# new-mainboard.net
KiCad netlist of a schematic drawn in EAGLE
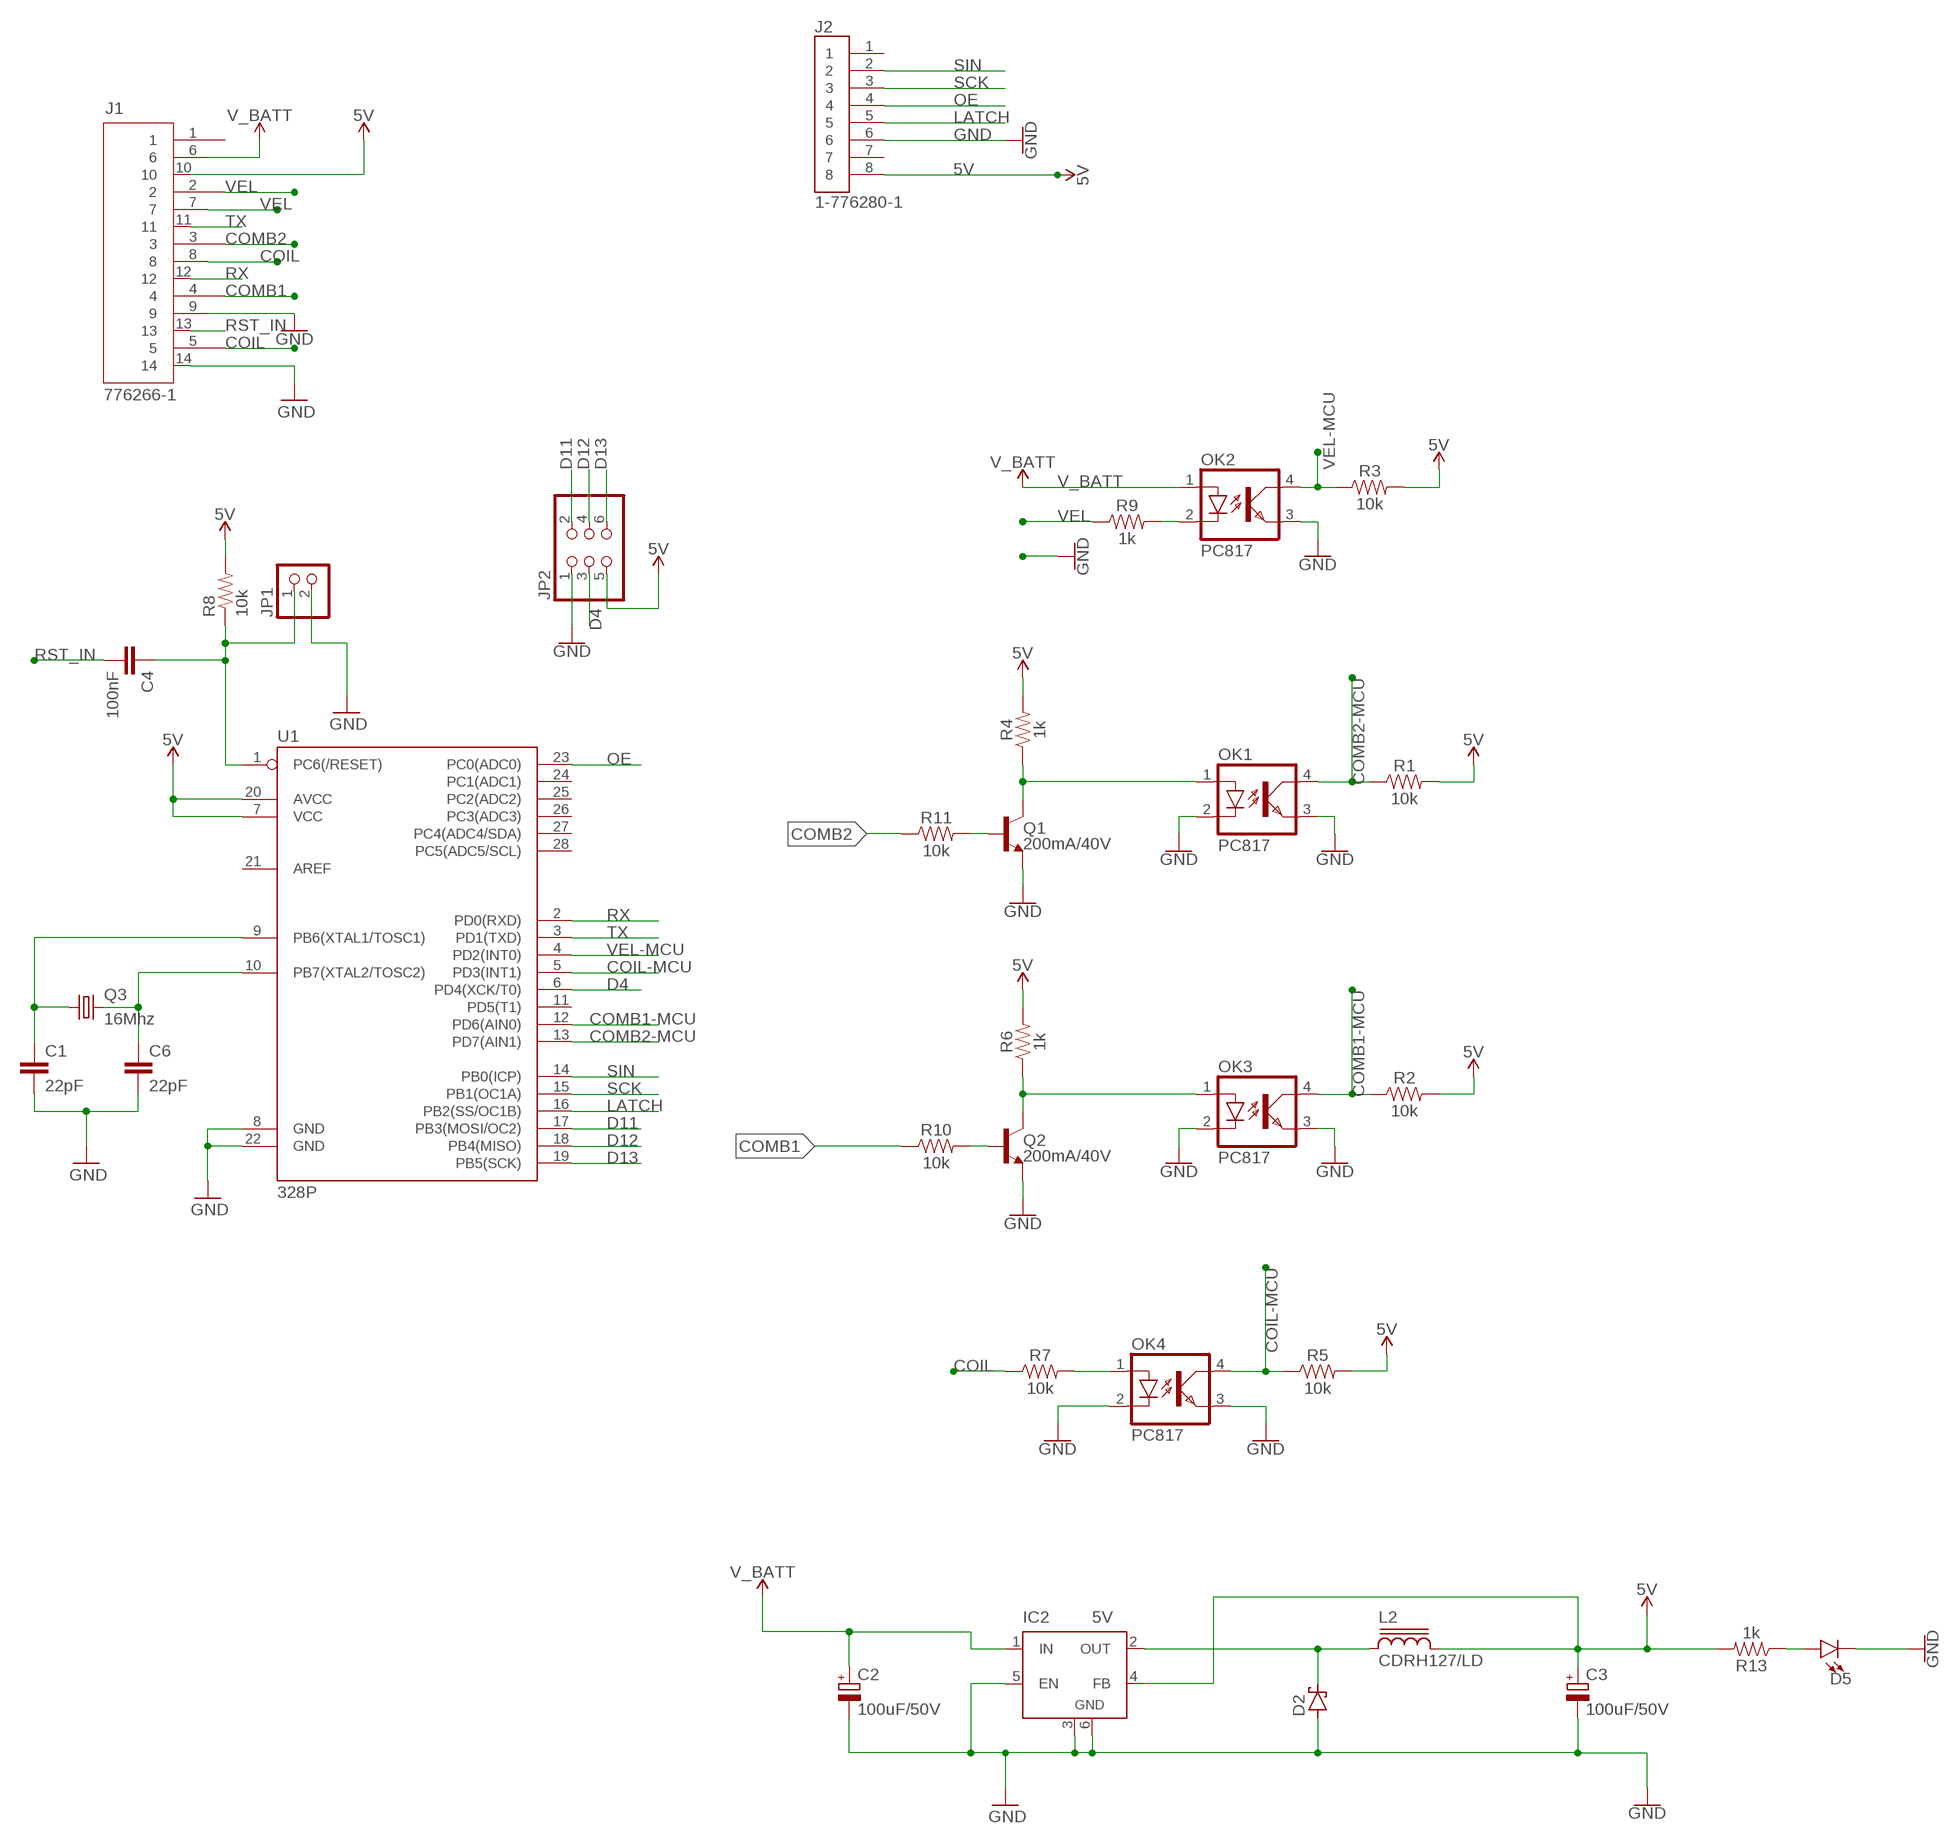
[diagram p0: schematic, sheet 1]

(export (version "E")
  (design (tool "Eeschema 10.0.6"))
  (components
    (comp (ref "C1")
      (value "22pF")
      (footprint "eagle-import:CAP-PTH-2.54")
      (libsource (lib "eagle-import") (part "22PF-PTH-2.54MM-200V-5%"))
    )
    (comp (ref "C2")
      (value "100uF/50V")
      (footprint "eagle-import:E3,5-8")
      (libsource (lib "eagle-import") (part "CPOL-EUE3.5-8"))
    )
    (comp (ref "C3")
      (value "100uF/50V")
      (footprint "eagle-import:E3,5-8")
      (libsource (lib "eagle-import") (part "CPOL-EUE3.5-8"))
    )
    (comp (ref "C4")
      (value "100nF")
      (footprint "eagle-import:CAP-PTH-2.54")
      (libsource (lib "eagle-import") (part "22PF-PTH-2.54MM-200V-5%"))
    )
    (comp (ref "C6")
      (value "22pF")
      (footprint "eagle-import:CAP-PTH-2.54")
      (libsource (lib "eagle-import") (part "22PF-PTH-2.54MM-200V-5%"))
    )
    (comp (ref "D2")
      (value "SCHOTTKY-DIODESMD")
      (footprint "eagle-import:SMB")
      (libsource (lib "eagle-import") (part "SCHOTTKY-DIODESMD"))
    )
    (comp (ref "D5")
      (value "LED3MM")
      (footprint "eagle-import:LED_3MM")
      (libsource (lib "eagle-import") (part "LED3MM"))
    )
    (comp (ref "IC2")
      (value "5V")
      (footprint "eagle-import:TO263-5")
      (libsource (lib "eagle-import") (part "LM2596S"))
    )
    (comp (ref "J1")
      (value "776266-1")
      (footprint "eagle-import:TE_776266-1")
      (fields (field (name "MANUFACTURER") "TE CONNECTIVITY"))
      (libsource (lib "eagle-import") (part "776266-1"))
    )
    (comp (ref "J2")
      (value "1-776280-1")
      (footprint "eagle-import:TE_1-776280-1")
      (fields (field (name "MANUFACTURER") "TE Connectivity"))
      (libsource (lib "eagle-import") (part "1-776280-1"))
    )
    (comp (ref "JP1")
      (value "PINHD-1X2")
      (footprint "eagle-import:1X02")
      (libsource (lib "eagle-import") (part "PINHD-1X2"))
    )
    (comp (ref "JP2")
      (value "PINHD-2X3")
      (footprint "eagle-import:2X03")
      (libsource (lib "eagle-import") (part "PINHD-2X3"))
    )
    (comp (ref "L2")
      (value "CDRH127/LD")
      (footprint "eagle-import:CDRH127_LD")
      (libsource (lib "eagle-import") (part "CDRH127/LD"))
    )
    (comp (ref "OK1")
      (value "PC817")
      (footprint "eagle-import:DIL04")
      (fields (field (name "MPN") "PC817X4J000F"))
      (libsource (lib "eagle-import") (part "PC817"))
    )
    (comp (ref "OK2")
      (value "PC817")
      (footprint "eagle-import:DIL04")
      (fields (field (name "MPN") "PC817X4J000F"))
      (libsource (lib "eagle-import") (part "PC817"))
    )
    (comp (ref "OK3")
      (value "PC817")
      (footprint "eagle-import:DIL04")
      (fields (field (name "MPN") "PC817X4J000F"))
      (libsource (lib "eagle-import") (part "PC817"))
    )
    (comp (ref "OK4")
      (value "PC817")
      (footprint "eagle-import:DIL04")
      (fields (field (name "MPN") "PC817X4J000F"))
      (libsource (lib "eagle-import") (part "PC817"))
    )
    (comp (ref "Q1")
      (value "200mA/40V")
      (footprint "eagle-import:TO-92")
      (libsource (lib "eagle-import") (part "TRANS_NPN-2N3904"))
    )
    (comp (ref "Q2")
      (value "200mA/40V")
      (footprint "eagle-import:TO-92")
      (libsource (lib "eagle-import") (part "TRANS_NPN-2N3904"))
    )
    (comp (ref "Q3")
      (value "16Mhz")
      (footprint "eagle-import:HC49U-V")
      (libsource (lib "eagle-import") (part "CRYSTALHC49U-V"))
    )
    (comp (ref "R1")
      (value "10k")
      (footprint "eagle-import:AXIAL-0.3")
      (libsource (lib "eagle-import") (part "10KOHM-HORIZ-1/4W-5%"))
    )
    (comp (ref "R2")
      (value "10k")
      (footprint "eagle-import:AXIAL-0.3")
      (libsource (lib "eagle-import") (part "10KOHM-HORIZ-1/4W-5%"))
    )
    (comp (ref "R3")
      (value "10k")
      (footprint "eagle-import:AXIAL-0.3")
      (libsource (lib "eagle-import") (part "10KOHM-HORIZ-1/4W-5%"))
    )
    (comp (ref "R4")
      (value "1k")
      (footprint "eagle-import:AXIAL-0.3")
      (libsource (lib "eagle-import") (part "1KOHM-HORIZ-1/4W-5%"))
    )
    (comp (ref "R5")
      (value "10k")
      (footprint "eagle-import:AXIAL-0.3")
      (libsource (lib "eagle-import") (part "10KOHM-HORIZ-1/4W-5%"))
    )
    (comp (ref "R6")
      (value "1k")
      (footprint "eagle-import:AXIAL-0.3")
      (libsource (lib "eagle-import") (part "1KOHM-HORIZ-1/4W-5%"))
    )
    (comp (ref "R7")
      (value "10k")
      (footprint "eagle-import:AXIAL-0.3")
      (libsource (lib "eagle-import") (part "10KOHM-HORIZ-1/4W-5%"))
    )
    (comp (ref "R8")
      (value "10k")
      (footprint "eagle-import:AXIAL-0.3")
      (libsource (lib "eagle-import") (part "SparkFun-Resistors_532_10KOHM-HORIZ-1/4W-5%"))
    )
    (comp (ref "R9")
      (value "1k")
      (footprint "eagle-import:AXIAL-0.3")
      (libsource (lib "eagle-import") (part "1KOHM-HORIZ-1/4W-5%"))
    )
    (comp (ref "R10")
      (value "10k")
      (footprint "eagle-import:AXIAL-0.3")
      (libsource (lib "eagle-import") (part "10KOHM-HORIZ-1/4W-5%"))
    )
    (comp (ref "R11")
      (value "10k")
      (footprint "eagle-import:AXIAL-0.3")
      (libsource (lib "eagle-import") (part "10KOHM-HORIZ-1/4W-5%"))
    )
    (comp (ref "R13")
      (value "1k")
      (footprint "eagle-import:AXIAL-0.3")
      (libsource (lib "eagle-import") (part "1KOHM-HORIZ-1/4W-5%"))
    )
    (comp (ref "U1")
      (value "328P")
      (footprint "eagle-import:DIP28")
      (libsource (lib "eagle-import") (part "ATMEGA328P_PDIP"))
    )
  )
  (nets
    (net (code "1") (name "/COIL") (class "Default")
      (node (ref "J1") (pin "5") (pinfunction "5_5") (pintype "passive"))
      (node (ref "J1") (pin "8") (pinfunction "8_8") (pintype "passive"))
      (node (ref "R7") (pin "P$1") (pinfunction "1_P$1") (pintype "passive"))
    )
    (net (code "2") (name "/COIL-MCU") (class "Default")
      (node (ref "OK4") (pin "4") (pinfunction "COL_4") (pintype "passive"))
      (node (ref "R5") (pin "P$1") (pinfunction "1_P$1") (pintype "passive"))
      (node (ref "U1") (pin "5") (pinfunction "PD3(INT1)_5") (pintype "bidirectional"))
    )
    (net (code "3") (name "/COMB1-MCU") (class "Default")
      (node (ref "OK3") (pin "4") (pinfunction "COL_4") (pintype "passive"))
      (node (ref "R2") (pin "P$1") (pinfunction "1_P$1") (pintype "passive"))
      (node (ref "U1") (pin "12") (pinfunction "PD6(AIN0)_12") (pintype "bidirectional"))
    )
    (net (code "4") (name "/COMB2-MCU") (class "Default")
      (node (ref "OK1") (pin "4") (pinfunction "COL_4") (pintype "passive"))
      (node (ref "R1") (pin "P$1") (pinfunction "1_P$1") (pintype "passive"))
      (node (ref "U1") (pin "13") (pinfunction "PD7(AIN1)_13") (pintype "bidirectional"))
    )
    (net (code "5") (name "/D4") (class "Default")
      (node (ref "JP2") (pin "3") (pinfunction "3_3") (pintype "passive"))
      (node (ref "U1") (pin "6") (pinfunction "PD4(XCK/T0)_6") (pintype "bidirectional"))
    )
    (net (code "6") (name "/D11") (class "Default")
      (node (ref "JP2") (pin "2") (pinfunction "2_2") (pintype "passive"))
      (node (ref "U1") (pin "17") (pinfunction "PB3(MOSI/OC2)_17") (pintype "bidirectional"))
    )
    (net (code "7") (name "/D12") (class "Default")
      (node (ref "JP2") (pin "4") (pinfunction "4_4") (pintype "passive"))
      (node (ref "U1") (pin "18") (pinfunction "PB4(MISO)_18") (pintype "bidirectional"))
    )
    (net (code "8") (name "/D13") (class "Default")
      (node (ref "JP2") (pin "6") (pinfunction "6_6") (pintype "passive"))
      (node (ref "U1") (pin "19") (pinfunction "PB5(SCK)_19") (pintype "bidirectional"))
    )
    (net (code "9") (name "/LATCH") (class "Default")
      (node (ref "J2") (pin "5") (pinfunction "5_5") (pintype "passive"))
      (node (ref "U1") (pin "16") (pinfunction "PB2(SS/OC1B)_16") (pintype "bidirectional"))
    )
    (net (code "10") (name "/OE") (class "Default")
      (node (ref "J2") (pin "4") (pinfunction "4_4") (pintype "passive"))
      (node (ref "U1") (pin "23") (pinfunction "PC0(ADC0)_23") (pintype "bidirectional"))
    )
    (net (code "11") (name "/RST_IN") (class "Default")
      (node (ref "C4") (pin "2") (pinfunction "2_2") (pintype "passive"))
      (node (ref "J1") (pin "13") (pinfunction "13_13") (pintype "passive"))
    )
    (net (code "12") (name "/RX") (class "Default")
      (node (ref "J1") (pin "12") (pinfunction "12_12") (pintype "passive"))
      (node (ref "U1") (pin "2") (pinfunction "PD0(RXD)_2") (pintype "bidirectional"))
    )
    (net (code "13") (name "/SCK") (class "Default")
      (node (ref "J2") (pin "3") (pinfunction "3_3") (pintype "passive"))
      (node (ref "U1") (pin "15") (pinfunction "PB1(OC1A)_15") (pintype "bidirectional"))
    )
    (net (code "14") (name "/SIN") (class "Default")
      (node (ref "J2") (pin "2") (pinfunction "2_2") (pintype "passive"))
      (node (ref "U1") (pin "14") (pinfunction "PB0(ICP)_14") (pintype "bidirectional"))
    )
    (net (code "15") (name "/TX") (class "Default")
      (node (ref "J1") (pin "11") (pinfunction "11_11") (pintype "passive"))
      (node (ref "U1") (pin "3") (pinfunction "PD1(TXD)_3") (pintype "bidirectional"))
    )
    (net (code "16") (name "/VEL") (class "Default")
      (node (ref "J1") (pin "2") (pinfunction "2_2") (pintype "passive"))
      (node (ref "J1") (pin "7") (pinfunction "7_7") (pintype "passive"))
      (node (ref "R9") (pin "P$1") (pinfunction "1_P$1") (pintype "passive"))
    )
    (net (code "17") (name "/VEL-MCU") (class "Default")
      (node (ref "OK2") (pin "4") (pinfunction "COL_4") (pintype "passive"))
      (node (ref "R3") (pin "P$1") (pinfunction "1_P$1") (pintype "passive"))
      (node (ref "U1") (pin "4") (pinfunction "PD2(INT0)_4") (pintype "bidirectional"))
    )
    (net (code "18") (name "5V") (class "Default")
      (node (ref "C3") (pin "+") (pinfunction "+_+") (pintype "passive"))
      (node (ref "IC2") (pin "4") (pinfunction "FB_4") (pintype "input"))
      (node (ref "J1") (pin "10") (pinfunction "10_10") (pintype "passive"))
      (node (ref "J2") (pin "8") (pinfunction "8_8") (pintype "passive"))
      (node (ref "JP2") (pin "5") (pinfunction "5_5") (pintype "passive"))
      (node (ref "L2") (pin "2") (pinfunction "2_2") (pintype "passive"))
      (node (ref "R1") (pin "P$2") (pinfunction "2_P$2") (pintype "passive"))
      (node (ref "R13") (pin "P$2") (pinfunction "2_P$2") (pintype "passive"))
      (node (ref "R2") (pin "P$2") (pinfunction "2_P$2") (pintype "passive"))
      (node (ref "R3") (pin "P$2") (pinfunction "2_P$2") (pintype "passive"))
      (node (ref "R4") (pin "P$2") (pinfunction "2_P$2") (pintype "passive"))
      (node (ref "R5") (pin "P$2") (pinfunction "2_P$2") (pintype "passive"))
      (node (ref "R6") (pin "P$2") (pinfunction "2_P$2") (pintype "passive"))
      (node (ref "R8") (pin "P$2") (pinfunction "2_P$2") (pintype "passive"))
      (node (ref "U1") (pin "20") (pinfunction "AVCC_20") (pintype "bidirectional"))
      (node (ref "U1") (pin "7") (pinfunction "VCC_7") (pintype "bidirectional"))
    )
    (net (code "19") (name "COMB1") (class "Default")
      (node (ref "J1") (pin "4") (pinfunction "4_4") (pintype "passive"))
      (node (ref "R10") (pin "P$1") (pinfunction "1_P$1") (pintype "passive"))
    )
    (net (code "20") (name "COMB2") (class "Default")
      (node (ref "J1") (pin "3") (pinfunction "3_3") (pintype "passive"))
      (node (ref "R11") (pin "P$1") (pinfunction "1_P$1") (pintype "passive"))
    )
    (net (code "21") (name "GND") (class "Default")
      (node (ref "C1") (pin "2") (pinfunction "2_2") (pintype "passive"))
      (node (ref "C2") (pin "-") (pinfunction "-_-") (pintype "passive"))
      (node (ref "C3") (pin "-") (pinfunction "-_-") (pintype "passive"))
      (node (ref "C6") (pin "2") (pinfunction "2_2") (pintype "passive"))
      (node (ref "D2") (pin "A") (pinfunction "A_A") (pintype "passive"))
      (node (ref "D5") (pin "K") (pinfunction "C_K") (pintype "passive"))
      (node (ref "IC2") (pin "3") (pinfunction "GND_3") (pintype "power_in"))
      (node (ref "IC2") (pin "5") (pinfunction "EN_5") (pintype "input"))
      (node (ref "IC2") (pin "6") (pinfunction "GND_6") (pintype "power_in"))
      (node (ref "J1") (pin "14") (pinfunction "14_14") (pintype "passive"))
      (node (ref "J1") (pin "9") (pinfunction "9_9") (pintype "passive"))
      (node (ref "J2") (pin "6") (pinfunction "6_6") (pintype "passive"))
      (node (ref "JP1") (pin "2") (pinfunction "2_2") (pintype "passive"))
      (node (ref "JP2") (pin "1") (pinfunction "1_1") (pintype "passive"))
      (node (ref "OK1") (pin "2") (pinfunction "C_2") (pintype "passive"))
      (node (ref "OK1") (pin "3") (pinfunction "EMIT_3") (pintype "passive"))
      (node (ref "OK2") (pin "3") (pinfunction "EMIT_3") (pintype "passive"))
      (node (ref "OK3") (pin "2") (pinfunction "C_2") (pintype "passive"))
      (node (ref "OK3") (pin "3") (pinfunction "EMIT_3") (pintype "passive"))
      (node (ref "OK4") (pin "2") (pinfunction "C_2") (pintype "passive"))
      (node (ref "OK4") (pin "3") (pinfunction "EMIT_3") (pintype "passive"))
      (node (ref "Q1") (pin "1") (pinfunction "E_1") (pintype "passive"))
      (node (ref "Q2") (pin "1") (pinfunction "E_1") (pintype "passive"))
      (node (ref "U1") (pin "22") (pinfunction "GND_22") (pintype "bidirectional"))
      (node (ref "U1") (pin "8") (pinfunction "GND_8") (pintype "bidirectional"))
    )
    (net (code "22") (name "Net-(IC2-OUT)") (class "Default")
      (node (ref "D2") (pin "C") (pinfunction "C_C") (pintype "passive"))
      (node (ref "IC2") (pin "2") (pinfunction "OUT_2") (pintype "output"))
      (node (ref "L2") (pin "1") (pinfunction "1_1") (pintype "passive"))
    )
    (net (code "23") (name "Net-(OK1-A)") (class "Default")
      (node (ref "OK1") (pin "1") (pinfunction "A_1") (pintype "passive"))
      (node (ref "Q1") (pin "3") (pinfunction "C_3") (pintype "passive"))
      (node (ref "R4") (pin "P$1") (pinfunction "1_P$1") (pintype "passive"))
    )
    (net (code "24") (name "Net-(OK2-C)") (class "Default")
      (node (ref "OK2") (pin "2") (pinfunction "C_2") (pintype "passive"))
      (node (ref "R9") (pin "P$2") (pinfunction "2_P$2") (pintype "passive"))
    )
    (net (code "25") (name "Net-(OK3-A)") (class "Default")
      (node (ref "OK3") (pin "1") (pinfunction "A_1") (pintype "passive"))
      (node (ref "Q2") (pin "3") (pinfunction "C_3") (pintype "passive"))
      (node (ref "R6") (pin "P$1") (pinfunction "1_P$1") (pintype "passive"))
    )
    (net (code "26") (name "Net-(OK4-A)") (class "Default")
      (node (ref "OK4") (pin "1") (pinfunction "A_1") (pintype "passive"))
      (node (ref "R7") (pin "P$2") (pinfunction "2_P$2") (pintype "passive"))
    )
    (net (code "27") (name "Net-(Q1-B)") (class "Default")
      (node (ref "Q1") (pin "2") (pinfunction "B_2") (pintype "passive"))
      (node (ref "R11") (pin "P$2") (pinfunction "2_P$2") (pintype "passive"))
    )
    (net (code "28") (name "Net-(Q2-B)") (class "Default")
      (node (ref "Q2") (pin "2") (pinfunction "B_2") (pintype "passive"))
      (node (ref "R10") (pin "P$2") (pinfunction "2_P$2") (pintype "passive"))
    )
    (net (code "29") (name "Net-(R8-1)") (class "Default")
      (node (ref "C4") (pin "1") (pinfunction "1_1") (pintype "passive"))
      (node (ref "JP1") (pin "1") (pinfunction "1_1") (pintype "passive"))
      (node (ref "R8") (pin "P$1") (pinfunction "1_P$1") (pintype "passive"))
      (node (ref "U1") (pin "1") (pinfunction "PC6(/RESET)_1") (pintype "bidirectional"))
    )
    (net (code "30") (name "Net-(R13-1)") (class "Default")
      (node (ref "D5") (pin "A") (pinfunction "A_A") (pintype "passive"))
      (node (ref "R13") (pin "P$1") (pinfunction "1_P$1") (pintype "passive"))
    )
    (net (code "31") (name "Net-(U1-PB6(XTAL1{slash}TOSC1))") (class "Default")
      (node (ref "C1") (pin "1") (pinfunction "1_1") (pintype "passive"))
      (node (ref "Q3") (pin "1") (pinfunction "1_1") (pintype "passive"))
      (node (ref "U1") (pin "9") (pinfunction "PB6(XTAL1/TOSC1)_9") (pintype "bidirectional"))
    )
    (net (code "32") (name "Net-(U1-PB7(XTAL2{slash}TOSC2))") (class "Default")
      (node (ref "C6") (pin "1") (pinfunction "1_1") (pintype "passive"))
      (node (ref "Q3") (pin "2") (pinfunction "2_2") (pintype "passive"))
      (node (ref "U1") (pin "10") (pinfunction "PB7(XTAL2/TOSC2)_10") (pintype "bidirectional"))
    )
    (net (code "33") (name "V_BATT") (class "Default")
      (node (ref "C2") (pin "+") (pinfunction "+_+") (pintype "passive"))
      (node (ref "IC2") (pin "1") (pinfunction "IN_1") (pintype "input"))
      (node (ref "J1") (pin "6") (pinfunction "6_6") (pintype "passive"))
      (node (ref "OK2") (pin "1") (pinfunction "A_1") (pintype "passive"))
    )
    (net (code "34") (name "unconnected-(J1-Pad1)") (class "Default")
      (node (ref "J1") (pin "1") (pinfunction "1_1") (pintype "passive"))
    )
    (net (code "35") (name "unconnected-(J2-Pad1)") (class "Default")
      (node (ref "J2") (pin "1") (pinfunction "1_1") (pintype "passive"))
    )
    (net (code "36") (name "unconnected-(J2-Pad7)") (class "Default")
      (node (ref "J2") (pin "7") (pinfunction "7_7") (pintype "passive"))
    )
    (net (code "37") (name "unconnected-(U1-AREF-Pad21)") (class "Default")
      (node (ref "U1") (pin "21") (pinfunction "AREF_21") (pintype "bidirectional"))
    )
    (net (code "38") (name "unconnected-(U1-PC1(ADC1)-Pad24)") (class "Default")
      (node (ref "U1") (pin "24") (pinfunction "PC1(ADC1)_24") (pintype "bidirectional"))
    )
    (net (code "39") (name "unconnected-(U1-PC2(ADC2)-Pad25)") (class "Default")
      (node (ref "U1") (pin "25") (pinfunction "PC2(ADC2)_25") (pintype "bidirectional"))
    )
    (net (code "40") (name "unconnected-(U1-PC3(ADC3)-Pad26)") (class "Default")
      (node (ref "U1") (pin "26") (pinfunction "PC3(ADC3)_26") (pintype "bidirectional"))
    )
    (net (code "41") (name "unconnected-(U1-PC4(ADC4{slash}SDA)-Pad27)") (class "Default")
      (node (ref "U1") (pin "27") (pinfunction "PC4(ADC4/SDA)_27") (pintype "bidirectional"))
    )
    (net (code "42") (name "unconnected-(U1-PC5(ADC5{slash}SCL)-Pad28)") (class "Default")
      (node (ref "U1") (pin "28") (pinfunction "PC5(ADC5/SCL)_28") (pintype "bidirectional"))
    )
    (net (code "43") (name "unconnected-(U1-PD5(T1)-Pad11)") (class "Default")
      (node (ref "U1") (pin "11") (pinfunction "PD5(T1)_11") (pintype "bidirectional"))
    )
  )
)
